# ProPrj_HSLinkTestBoard_2025-10-28.net
KiCad netlist of a schematic drawn in EasyEDA Pro
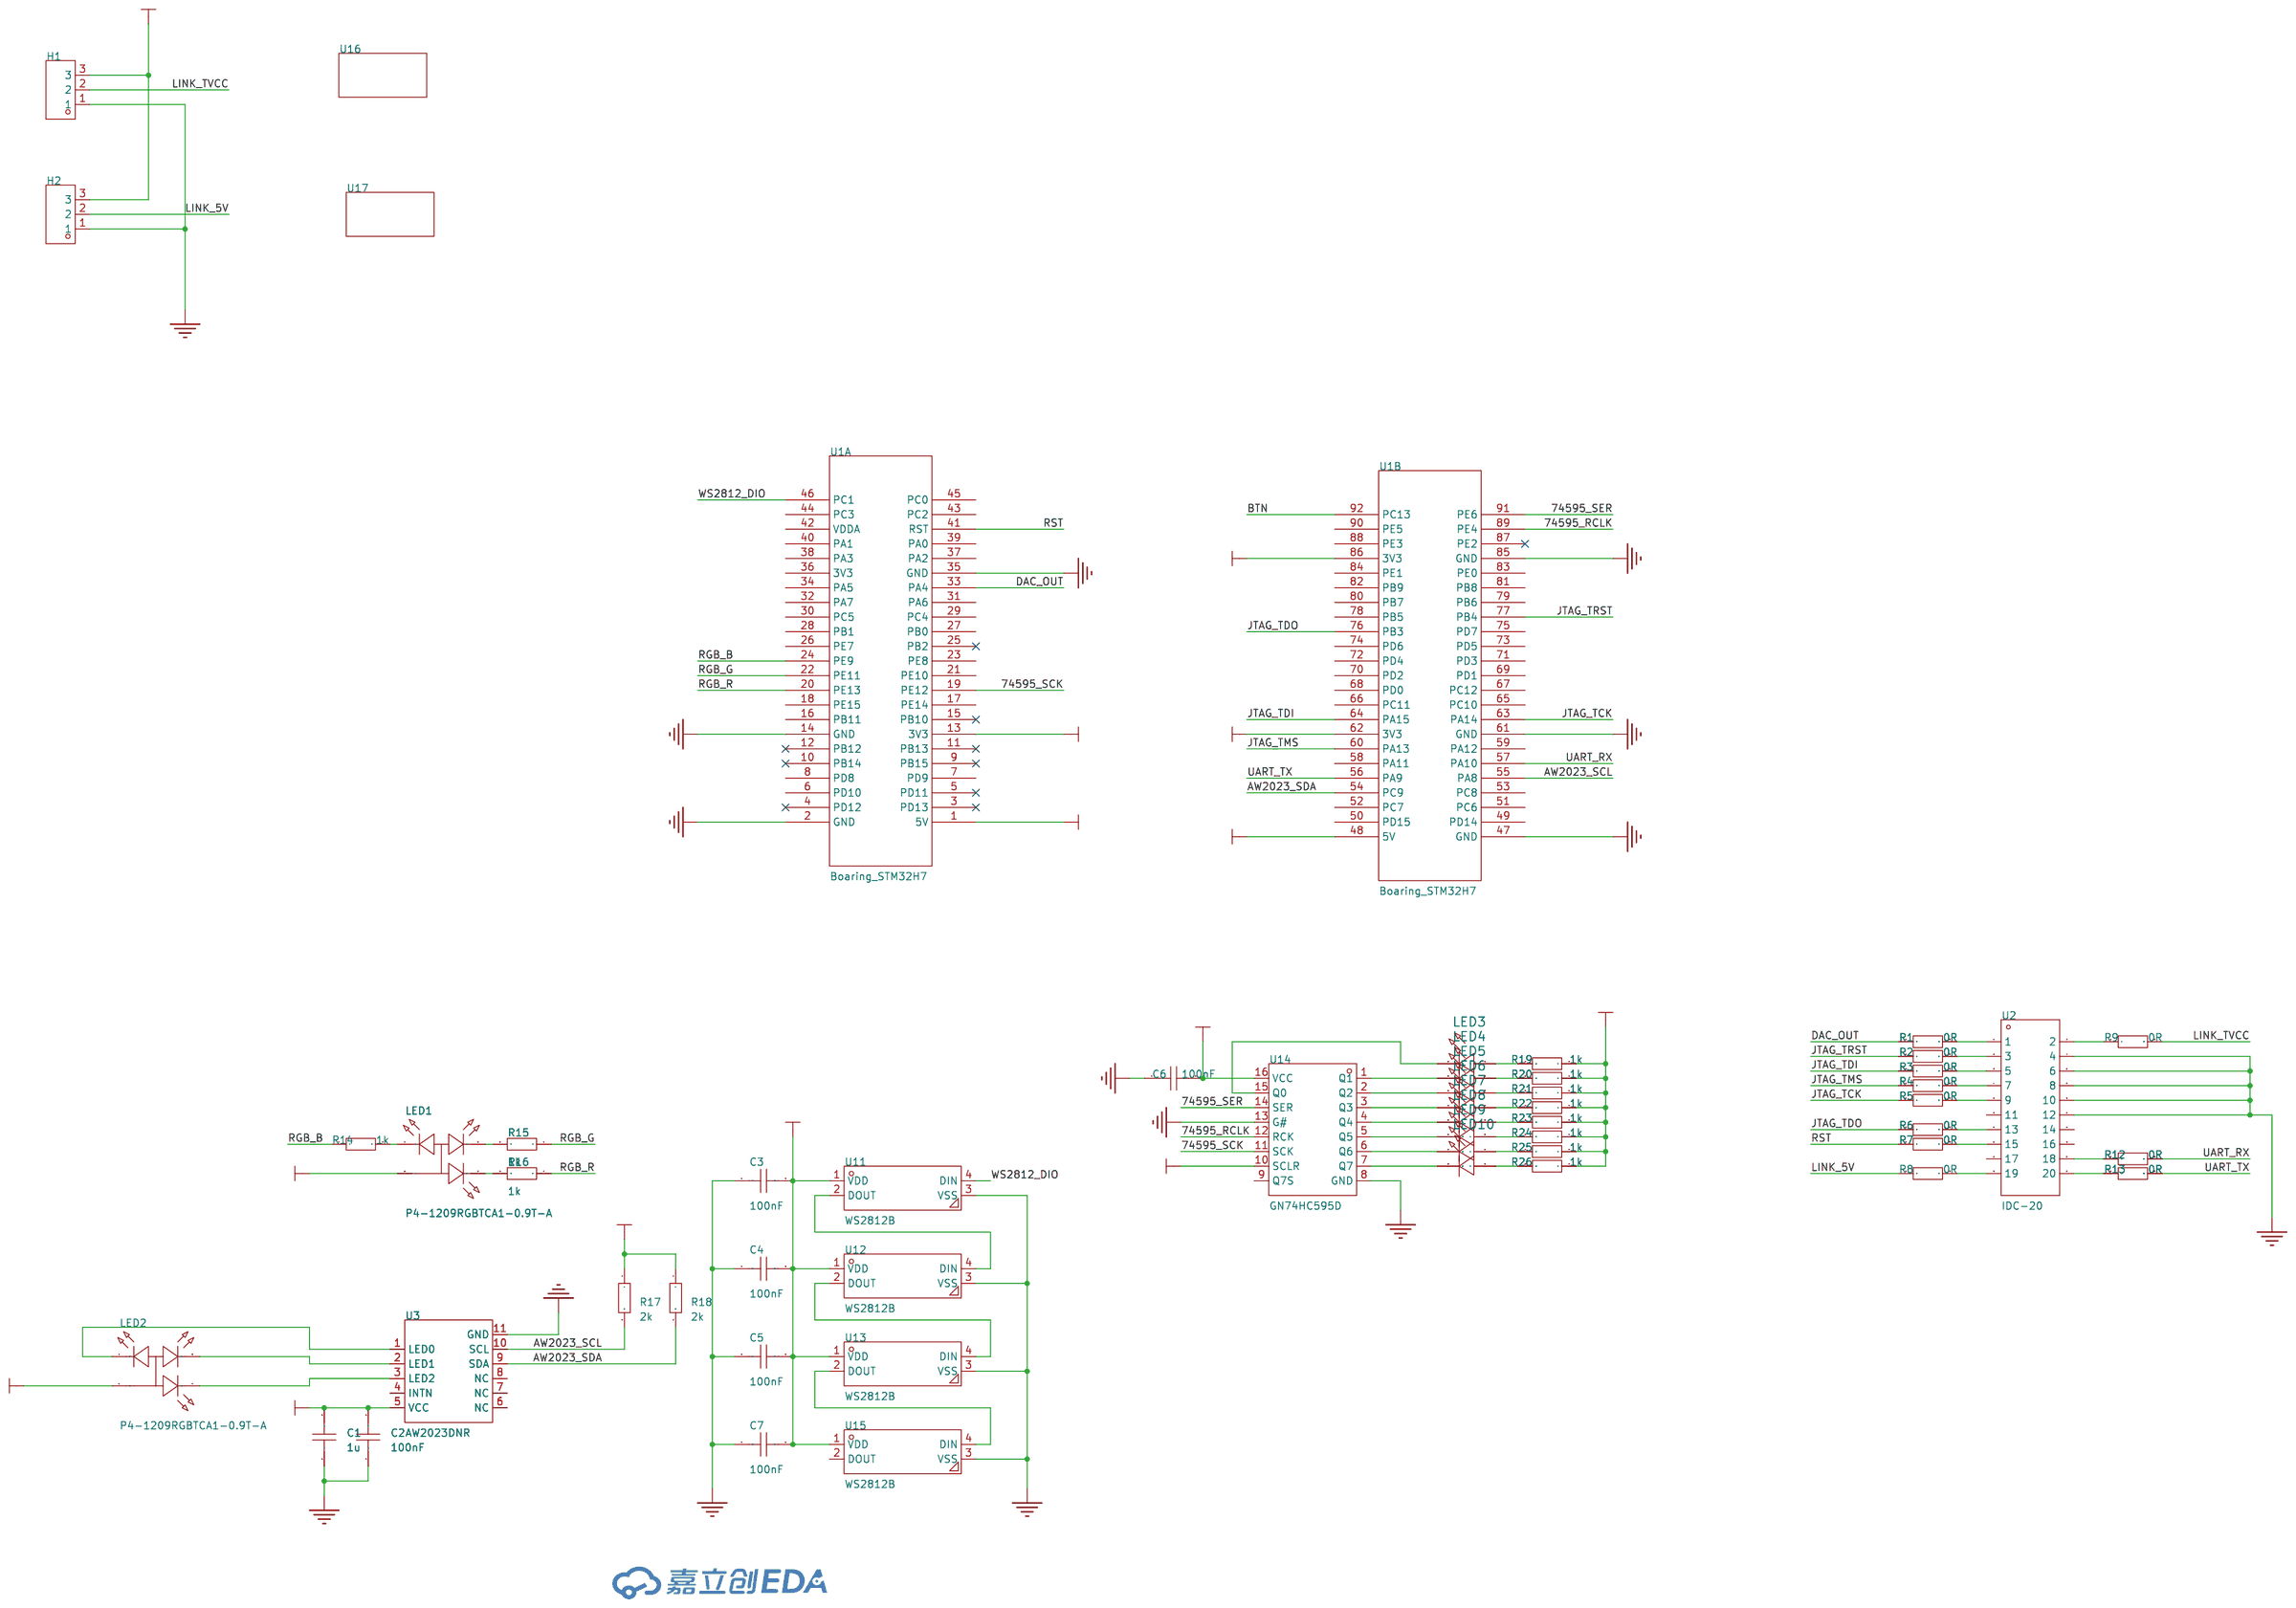
[diagram p0: schematic sheet]

(export (version "E")
  (design (tool "Eeschema 10.0.6"))
  (components
    (comp (ref "C1")
      (value "1u")
      (footprint "easyedapro:C0603")
      (libsource (lib "easyedapro") (part "CapAcitance"))
    )
    (comp (ref "C2")
      (value "100nF")
      (footprint "easyedapro:C0603")
      (libsource (lib "easyedapro") (part "CapAcitance"))
    )
    (comp (ref "C3")
      (value "100nF")
      (footprint "easyedapro:C0603")
      (libsource (lib "easyedapro") (part "CapAcitance"))
    )
    (comp (ref "C4")
      (value "100nF")
      (footprint "easyedapro:C0603")
      (libsource (lib "easyedapro") (part "CapAcitance"))
    )
    (comp (ref "C5")
      (value "100nF")
      (footprint "easyedapro:C0603")
      (libsource (lib "easyedapro") (part "CapAcitance"))
    )
    (comp (ref "C6")
      (value "100nF")
      (footprint "easyedapro:C0603")
      (libsource (lib "easyedapro") (part "CapAcitance"))
    )
    (comp (ref "C7")
      (value "100nF")
      (footprint "easyedapro:C0603")
      (libsource (lib "easyedapro") (part "CapAcitance"))
    )
    (comp (ref "H1")
      (value "~")
      (footprint "easyedapro:HDR-TH_3P-P2.54-V-F")
      (libsource (lib "easyedapro") (part "PM254V-11-03-H85"))
    )
    (comp (ref "H2")
      (value "~")
      (footprint "easyedapro:HDR-TH_3P-P2.54-V-F")
      (libsource (lib "easyedapro") (part "PM254V-11-03-H85"))
    )
    (comp (ref "LED1")
      (value "P4-1209RGBTCA1-0.9T-A")
      (footprint "easyedapro:LED-SMD_4P-L3.2-W2.7-TL-CW")
      (fields (field (name "Manufacturer") "TUOZHAN(拓展光电)"))
      (libsource (lib "easyedapro") (part "P4-1209RGBTCA1-0.9T-A"))
    )
    (comp (ref "LED2")
      (value "P4-1209RGBTCA1-0.9T-A")
      (footprint "easyedapro:LED-SMD_4P-L3.2-W2.7-TL-CW")
      (fields (field (name "Manufacturer") "TUOZHAN(拓展光电)"))
      (libsource (lib "easyedapro") (part "P4-1209RGBTCA1-0.9T-A"))
    )
    (comp (ref "LED3")
      (value "~")
      (footprint "easyedapro:LED_0603")
      (libsource (lib "easyedapro") (part "LED_R"))
    )
    (comp (ref "LED4")
      (value "~")
      (footprint "easyedapro:LED_0603")
      (libsource (lib "easyedapro") (part "LED_R"))
    )
    (comp (ref "LED5")
      (value "~")
      (footprint "easyedapro:LED_0603")
      (libsource (lib "easyedapro") (part "LED_R"))
    )
    (comp (ref "LED6")
      (value "~")
      (footprint "easyedapro:LED_0603")
      (libsource (lib "easyedapro") (part "LED_R"))
    )
    (comp (ref "LED7")
      (value "~")
      (footprint "easyedapro:LED_0603")
      (libsource (lib "easyedapro") (part "LED_R"))
    )
    (comp (ref "LED8")
      (value "~")
      (footprint "easyedapro:LED_0603")
      (libsource (lib "easyedapro") (part "LED_R"))
    )
    (comp (ref "LED9")
      (value "~")
      (footprint "easyedapro:LED_0603")
      (libsource (lib "easyedapro") (part "LED_R"))
    )
    (comp (ref "LED10")
      (value "~")
      (footprint "easyedapro:LED_0603")
      (libsource (lib "easyedapro") (part "LED_R"))
    )
    (comp (ref "R1") (value "0R") (footprint "easyedapro:R0603") (libsource (lib "easyedapro") (part "电阻")))
    (comp (ref "R2") (value "0R") (footprint "easyedapro:R0603") (libsource (lib "easyedapro") (part "电阻")))
    (comp (ref "R3") (value "0R") (footprint "easyedapro:R0603") (libsource (lib "easyedapro") (part "电阻")))
    (comp (ref "R4") (value "0R") (footprint "easyedapro:R0603") (libsource (lib "easyedapro") (part "电阻")))
    (comp (ref "R5") (value "0R") (footprint "easyedapro:R0603") (libsource (lib "easyedapro") (part "电阻")))
    (comp (ref "R6") (value "0R") (footprint "easyedapro:R0603") (libsource (lib "easyedapro") (part "电阻")))
    (comp (ref "R7") (value "0R") (footprint "easyedapro:R0603") (libsource (lib "easyedapro") (part "电阻")))
    (comp (ref "R8") (value "0R") (footprint "easyedapro:R0603") (libsource (lib "easyedapro") (part "电阻")))
    (comp (ref "R9") (value "0R") (footprint "easyedapro:R0603") (libsource (lib "easyedapro") (part "电阻")))
    (comp (ref "R12") (value "0R") (footprint "easyedapro:R0603") (libsource (lib "easyedapro") (part "电阻")))
    (comp (ref "R13") (value "0R") (footprint "easyedapro:R0603") (libsource (lib "easyedapro") (part "电阻")))
    (comp (ref "R14") (value "1k") (footprint "easyedapro:R0603") (libsource (lib "easyedapro") (part "电阻")))
    (comp (ref "R15") (value "1k") (footprint "easyedapro:R0603") (libsource (lib "easyedapro") (part "电阻")))
    (comp (ref "R16") (value "1k") (footprint "easyedapro:R0603") (libsource (lib "easyedapro") (part "电阻")))
    (comp (ref "R17") (value "2k") (footprint "easyedapro:R0603") (libsource (lib "easyedapro") (part "电阻")))
    (comp (ref "R18") (value "2k") (footprint "easyedapro:R0603") (libsource (lib "easyedapro") (part "电阻")))
    (comp (ref "R19") (value "1k") (footprint "easyedapro:R0603") (libsource (lib "easyedapro") (part "电阻")))
    (comp (ref "R20") (value "1k") (footprint "easyedapro:R0603") (libsource (lib "easyedapro") (part "电阻")))
    (comp (ref "R21") (value "1k") (footprint "easyedapro:R0603") (libsource (lib "easyedapro") (part "电阻")))
    (comp (ref "R22") (value "1k") (footprint "easyedapro:R0603") (libsource (lib "easyedapro") (part "电阻")))
    (comp (ref "R23") (value "1k") (footprint "easyedapro:R0603") (libsource (lib "easyedapro") (part "电阻")))
    (comp (ref "R24") (value "1k") (footprint "easyedapro:R0603") (libsource (lib "easyedapro") (part "电阻")))
    (comp (ref "R25") (value "1k") (footprint "easyedapro:R0603") (libsource (lib "easyedapro") (part "电阻")))
    (comp (ref "R26") (value "1k") (footprint "easyedapro:R0603") (libsource (lib "easyedapro") (part "电阻")))
    (comp (ref "U1")
      (value "Boaring_STM32H7")
      (footprint "easyedapro:Boaring_STM32H7")
      (libsource (lib "easyedapro") (part "Boaring_STM32H7"))
    )
    (comp (ref "U2")
      (value "IDC-20")
      (footprint "easyedapro:IDC-TH_20P-P2.54-V-R2-C10-S2.54")
      (libsource (lib "easyedapro") (part "IDC-20"))
    )
    (comp (ref "U3")
      (value "AW2023DNR")
      (footprint "easyedapro:DFN-10_L2.0-W2.0-P0.40-BL-EP")
      (fields (field (name "Manufacturer") "AWINIC(艾为)"))
      (libsource (lib "easyedapro") (part "AW2023DNR"))
    )
    (comp (ref "U11")
      (value "WS2812B")
      (footprint "easyedapro:LED-SMD_4P-L5.0-W5.0-TL")
      (libsource (lib "easyedapro") (part "WS2812B_C9900106807"))
    )
    (comp (ref "U12")
      (value "WS2812B")
      (footprint "easyedapro:LED-SMD_4P-L5.0-W5.0-TL")
      (libsource (lib "easyedapro") (part "WS2812B_C9900106807"))
    )
    (comp (ref "U13")
      (value "WS2812B")
      (footprint "easyedapro:LED-SMD_4P-L5.0-W5.0-TL")
      (libsource (lib "easyedapro") (part "WS2812B_C9900106807"))
    )
    (comp (ref "U14")
      (value "GN74HC595D")
      (footprint "easyedapro:SOP-16_L9.9-W3.9-P1.27-LS6.0-BL")
      (description "低噪声、低功耗、高速的COMS移位寄存器，能够驱动15个LS-TTL的负载。8位串行输入，并行输出的移位寄存器及带有三态输出控制的8位D行储存器。")
      (fields (field (name "Manufacturer") "GN(旌芯半导体)"))
      (libsource (lib "easyedapro") (part "GN74HC595D"))
    )
    (comp (ref "U15")
      (value "WS2812B")
      (footprint "easyedapro:LED-SMD_4P-L5.0-W5.0-TL")
      (libsource (lib "easyedapro") (part "WS2812B_C9900106807"))
    )
    (comp (ref "U16")
      (value "~")
      (footprint "easyedapro:0.36寸裸表")
      (libsource (lib "easyedapro") (part "0.36裸表"))
    )
    (comp (ref "U17")
      (value "~")
      (footprint "easyedapro:0.36寸裸表")
      (libsource (lib "easyedapro") (part "0.36裸表"))
    )
  )
  (nets
    (net (code "1") (name "/74595_RCLK") (class "Default")
      (node (ref "U1") (pin "89") (pinfunction "PE4_89") (pintype "unspecified"))
      (node (ref "U14") (pin "12") (pinfunction "RCK_12") (pintype "unspecified"))
    )
    (net (code "2") (name "/74595_SCK") (class "Default")
      (node (ref "U1") (pin "19") (pinfunction "PE12_19") (pintype "unspecified"))
      (node (ref "U14") (pin "11") (pinfunction "SCK_11") (pintype "unspecified"))
    )
    (net (code "3") (name "/74595_SER") (class "Default")
      (node (ref "U1") (pin "91") (pinfunction "PE6_91") (pintype "unspecified"))
      (node (ref "U14") (pin "14") (pinfunction "SER_14") (pintype "unspecified"))
    )
    (net (code "4") (name "/AW2023_SCL") (class "Default")
      (node (ref "R17") (pin "2") (pinfunction "2_2") (pintype "input"))
      (node (ref "U1") (pin "55") (pinfunction "PA8_55") (pintype "unspecified"))
      (node (ref "U3") (pin "10") (pinfunction "SCL_10") (pintype "unspecified"))
    )
    (net (code "5") (name "/AW2023_SDA") (class "Default")
      (node (ref "R18") (pin "2") (pinfunction "2_2") (pintype "input"))
      (node (ref "U1") (pin "54") (pinfunction "PC9_54") (pintype "unspecified"))
      (node (ref "U3") (pin "9") (pinfunction "SDA_9") (pintype "unspecified"))
    )
    (net (code "6") (name "/BTN") (class "Default")
      (node (ref "U1") (pin "92") (pinfunction "PC13_92") (pintype "unspecified"))
    )
    (net (code "7") (name "/DAC_OUT") (class "Default")
      (node (ref "R1") (pin "1") (pinfunction "1_1") (pintype "input"))
      (node (ref "U1") (pin "33") (pinfunction "PA4_33") (pintype "unspecified"))
    )
    (net (code "8") (name "/JTAG_TCK") (class "Default")
      (node (ref "R5") (pin "1") (pinfunction "1_1") (pintype "input"))
      (node (ref "U1") (pin "63") (pinfunction "PA14_63") (pintype "unspecified"))
    )
    (net (code "9") (name "/JTAG_TDI") (class "Default")
      (node (ref "R3") (pin "1") (pinfunction "1_1") (pintype "input"))
      (node (ref "U1") (pin "64") (pinfunction "PA15_64") (pintype "unspecified"))
    )
    (net (code "10") (name "/JTAG_TDO") (class "Default")
      (node (ref "R6") (pin "1") (pinfunction "1_1") (pintype "input"))
      (node (ref "U1") (pin "76") (pinfunction "PB3_76") (pintype "unspecified"))
    )
    (net (code "11") (name "/JTAG_TMS") (class "Default")
      (node (ref "R4") (pin "1") (pinfunction "1_1") (pintype "input"))
      (node (ref "U1") (pin "60") (pinfunction "PA13_60") (pintype "unspecified"))
    )
    (net (code "12") (name "/JTAG_TRST") (class "Default")
      (node (ref "R2") (pin "1") (pinfunction "1_1") (pintype "input"))
      (node (ref "U1") (pin "77") (pinfunction "PB4_77") (pintype "unspecified"))
    )
    (net (code "13") (name "/LINK_5V") (class "Default")
      (node (ref "H2") (pin "2") (pinfunction "2_2") (pintype "unspecified"))
      (node (ref "R8") (pin "1") (pinfunction "1_1") (pintype "input"))
    )
    (net (code "14") (name "/LINK_TVCC") (class "Default")
      (node (ref "H1") (pin "2") (pinfunction "2_2") (pintype "unspecified"))
      (node (ref "R9") (pin "2") (pinfunction "2_2") (pintype "input"))
    )
    (net (code "15") (name "/RGB_B") (class "Default")
      (node (ref "R14") (pin "1") (pinfunction "1_1") (pintype "input"))
      (node (ref "U1") (pin "24") (pinfunction "PE9_24") (pintype "unspecified"))
    )
    (net (code "16") (name "/RGB_G") (class "Default")
      (node (ref "R15") (pin "1") (pinfunction "1_1") (pintype "input"))
      (node (ref "U1") (pin "22") (pinfunction "PE11_22") (pintype "unspecified"))
    )
    (net (code "17") (name "/RGB_R") (class "Default")
      (node (ref "R16") (pin "1") (pinfunction "1_1") (pintype "input"))
      (node (ref "U1") (pin "20") (pinfunction "PE13_20") (pintype "unspecified"))
    )
    (net (code "18") (name "/RST") (class "Default")
      (node (ref "R7") (pin "1") (pinfunction "1_1") (pintype "input"))
      (node (ref "U1") (pin "41") (pinfunction "RST_41") (pintype "unspecified"))
    )
    (net (code "19") (name "/UART_RX") (class "Default")
      (node (ref "R12") (pin "2") (pinfunction "2_2") (pintype "input"))
      (node (ref "U1") (pin "57") (pinfunction "PA10_57") (pintype "unspecified"))
    )
    (net (code "20") (name "/UART_TX") (class "Default")
      (node (ref "R13") (pin "2") (pinfunction "2_2") (pintype "input"))
      (node (ref "U1") (pin "56") (pinfunction "PA9_56") (pintype "unspecified"))
    )
    (net (code "21") (name "/WS2812_DIO") (class "Default")
      (node (ref "U1") (pin "46") (pinfunction "PC1_46") (pintype "unspecified"))
      (node (ref "U11") (pin "4") (pinfunction "DIN_4") (pintype "unspecified"))
    )
    (net (code "22") (name "3.3V") (class "Default")
      (node (ref "C1") (pin "2") (pinfunction "2_2") (pintype "input"))
      (node (ref "C2") (pin "2") (pinfunction "2_2") (pintype "input"))
      (node (ref "C6") (pin "2") (pinfunction "2_2") (pintype "input"))
      (node (ref "LED1") (pin "3") (pinfunction "A_3") (pintype "unspecified"))
      (node (ref "LED2") (pin "3") (pinfunction "A_3") (pintype "unspecified"))
      (node (ref "R17") (pin "1") (pinfunction "1_1") (pintype "input"))
      (node (ref "R18") (pin "1") (pinfunction "1_1") (pintype "input"))
      (node (ref "R19") (pin "1") (pinfunction "1_1") (pintype "input"))
      (node (ref "R20") (pin "1") (pinfunction "1_1") (pintype "input"))
      (node (ref "R21") (pin "1") (pinfunction "1_1") (pintype "input"))
      (node (ref "R22") (pin "1") (pinfunction "1_1") (pintype "input"))
      (node (ref "R23") (pin "1") (pinfunction "1_1") (pintype "input"))
      (node (ref "R24") (pin "1") (pinfunction "1_1") (pintype "input"))
      (node (ref "R25") (pin "1") (pinfunction "1_1") (pintype "input"))
      (node (ref "R26") (pin "1") (pinfunction "1_1") (pintype "input"))
      (node (ref "U1") (pin "13") (pinfunction "3V3_13") (pintype "unspecified"))
      (node (ref "U1") (pin "62") (pinfunction "3V3_62") (pintype "unspecified"))
      (node (ref "U1") (pin "86") (pinfunction "3V3_86") (pintype "unspecified"))
      (node (ref "U14") (pin "10") (pinfunction "SCLR_10") (pintype "unspecified"))
      (node (ref "U14") (pin "16") (pinfunction "VCC_16") (pintype "unspecified"))
      (node (ref "U3") (pin "5") (pinfunction "VCC_5") (pintype "unspecified"))
    )
    (net (code "23") (name "5V") (class "Default")
      (node (ref "C3") (pin "2") (pinfunction "2_2") (pintype "input"))
      (node (ref "C4") (pin "2") (pinfunction "2_2") (pintype "input"))
      (node (ref "C5") (pin "2") (pinfunction "2_2") (pintype "input"))
      (node (ref "C7") (pin "2") (pinfunction "2_2") (pintype "input"))
      (node (ref "H1") (pin "3") (pinfunction "3_3") (pintype "unspecified"))
      (node (ref "H2") (pin "3") (pinfunction "3_3") (pintype "unspecified"))
      (node (ref "U1") (pin "1") (pinfunction "5V_1") (pintype "unspecified"))
      (node (ref "U1") (pin "48") (pinfunction "5V_48") (pintype "unspecified"))
      (node (ref "U11") (pin "1") (pinfunction "VDD_1") (pintype "unspecified"))
      (node (ref "U12") (pin "1") (pinfunction "VDD_1") (pintype "unspecified"))
      (node (ref "U13") (pin "1") (pinfunction "VDD_1") (pintype "unspecified"))
      (node (ref "U15") (pin "1") (pinfunction "VDD_1") (pintype "unspecified"))
    )
    (net (code "24") (name "GND") (class "Default")
      (node (ref "C1") (pin "1") (pinfunction "1_1") (pintype "input"))
      (node (ref "C2") (pin "1") (pinfunction "1_1") (pintype "input"))
      (node (ref "C3") (pin "1") (pinfunction "1_1") (pintype "input"))
      (node (ref "C4") (pin "1") (pinfunction "1_1") (pintype "input"))
      (node (ref "C5") (pin "1") (pinfunction "1_1") (pintype "input"))
      (node (ref "C6") (pin "1") (pinfunction "1_1") (pintype "input"))
      (node (ref "C7") (pin "1") (pinfunction "1_1") (pintype "input"))
      (node (ref "H1") (pin "1") (pinfunction "1_1") (pintype "unspecified"))
      (node (ref "H2") (pin "1") (pinfunction "1_1") (pintype "unspecified"))
      (node (ref "U1") (pin "14") (pinfunction "GND_14") (pintype "unspecified"))
      (node (ref "U1") (pin "2") (pinfunction "GND_2") (pintype "unspecified"))
      (node (ref "U1") (pin "35") (pinfunction "GND_35") (pintype "unspecified"))
      (node (ref "U1") (pin "47") (pinfunction "GND_47") (pintype "unspecified"))
      (node (ref "U1") (pin "61") (pinfunction "GND_61") (pintype "unspecified"))
      (node (ref "U1") (pin "85") (pinfunction "GND_85") (pintype "unspecified"))
      (node (ref "U11") (pin "3") (pinfunction "VSS_3") (pintype "unspecified"))
      (node (ref "U12") (pin "3") (pinfunction "VSS_3") (pintype "unspecified"))
      (node (ref "U13") (pin "3") (pinfunction "VSS_3") (pintype "unspecified"))
      (node (ref "U14") (pin "13") (pinfunction "G#_13") (pintype "unspecified"))
      (node (ref "U14") (pin "8") (pinfunction "GND_8") (pintype "unspecified"))
      (node (ref "U15") (pin "3") (pinfunction "VSS_3") (pintype "unspecified"))
      (node (ref "U2") (pin "10") (pinfunction "10_10") (pintype "unspecified"))
      (node (ref "U2") (pin "12") (pinfunction "12_12") (pintype "unspecified"))
      (node (ref "U2") (pin "4") (pinfunction "4_4") (pintype "unspecified"))
      (node (ref "U2") (pin "6") (pinfunction "6_6") (pintype "unspecified"))
      (node (ref "U2") (pin "8") (pinfunction "8_8") (pintype "unspecified"))
      (node (ref "U3") (pin "11") (pinfunction "GND_11") (pintype "unspecified"))
    )
    (net (code "25") (name "Net-(LED1-K-Pad1)") (class "Default")
      (node (ref "LED1") (pin "1") (pinfunction "K_1") (pintype "unspecified"))
      (node (ref "R14") (pin "2") (pinfunction "2_2") (pintype "input"))
    )
    (net (code "26") (name "Net-(LED1-K-Pad2)") (class "Default")
      (node (ref "LED1") (pin "2") (pinfunction "K_2") (pintype "unspecified"))
      (node (ref "R15") (pin "2") (pinfunction "2_2") (pintype "input"))
    )
    (net (code "27") (name "Net-(LED1-K-Pad4)") (class "Default")
      (node (ref "LED1") (pin "4") (pinfunction "K_4") (pintype "unspecified"))
      (node (ref "R16") (pin "2") (pinfunction "2_2") (pintype "input"))
    )
    (net (code "28") (name "Net-(LED3-A)") (class "Default")
      (node (ref "LED3") (pin "2") (pinfunction "A_2") (pintype "input"))
      (node (ref "R19") (pin "2") (pinfunction "2_2") (pintype "input"))
    )
    (net (code "29") (name "Net-(LED3-C)") (class "Default")
      (node (ref "LED3") (pin "1") (pinfunction "C_1") (pintype "input"))
      (node (ref "U14") (pin "15") (pinfunction "Q0_15") (pintype "unspecified"))
    )
    (net (code "30") (name "Net-(LED4-A)") (class "Default")
      (node (ref "LED4") (pin "2") (pinfunction "A_2") (pintype "input"))
      (node (ref "R20") (pin "2") (pinfunction "2_2") (pintype "input"))
    )
    (net (code "31") (name "Net-(LED4-C)") (class "Default")
      (node (ref "LED4") (pin "1") (pinfunction "C_1") (pintype "input"))
      (node (ref "U14") (pin "1") (pinfunction "Q1_1") (pintype "unspecified"))
    )
    (net (code "32") (name "Net-(LED5-A)") (class "Default")
      (node (ref "LED5") (pin "2") (pinfunction "A_2") (pintype "input"))
      (node (ref "R21") (pin "2") (pinfunction "2_2") (pintype "input"))
    )
    (net (code "33") (name "Net-(LED5-C)") (class "Default")
      (node (ref "LED5") (pin "1") (pinfunction "C_1") (pintype "input"))
      (node (ref "U14") (pin "2") (pinfunction "Q2_2") (pintype "unspecified"))
    )
    (net (code "34") (name "Net-(LED6-A)") (class "Default")
      (node (ref "LED6") (pin "2") (pinfunction "A_2") (pintype "input"))
      (node (ref "R22") (pin "2") (pinfunction "2_2") (pintype "input"))
    )
    (net (code "35") (name "Net-(LED6-C)") (class "Default")
      (node (ref "LED6") (pin "1") (pinfunction "C_1") (pintype "input"))
      (node (ref "U14") (pin "3") (pinfunction "Q3_3") (pintype "unspecified"))
    )
    (net (code "36") (name "Net-(LED7-A)") (class "Default")
      (node (ref "LED7") (pin "2") (pinfunction "A_2") (pintype "input"))
      (node (ref "R23") (pin "2") (pinfunction "2_2") (pintype "input"))
    )
    (net (code "37") (name "Net-(LED7-C)") (class "Default")
      (node (ref "LED7") (pin "1") (pinfunction "C_1") (pintype "input"))
      (node (ref "U14") (pin "4") (pinfunction "Q4_4") (pintype "unspecified"))
    )
    (net (code "38") (name "Net-(LED8-A)") (class "Default")
      (node (ref "LED8") (pin "2") (pinfunction "A_2") (pintype "input"))
      (node (ref "R24") (pin "2") (pinfunction "2_2") (pintype "input"))
    )
    (net (code "39") (name "Net-(LED8-C)") (class "Default")
      (node (ref "LED8") (pin "1") (pinfunction "C_1") (pintype "input"))
      (node (ref "U14") (pin "5") (pinfunction "Q5_5") (pintype "unspecified"))
    )
    (net (code "40") (name "Net-(LED9-A)") (class "Default")
      (node (ref "LED9") (pin "2") (pinfunction "A_2") (pintype "input"))
      (node (ref "R25") (pin "2") (pinfunction "2_2") (pintype "input"))
    )
    (net (code "41") (name "Net-(LED9-C)") (class "Default")
      (node (ref "LED9") (pin "1") (pinfunction "C_1") (pintype "input"))
      (node (ref "U14") (pin "6") (pinfunction "Q6_6") (pintype "unspecified"))
    )
    (net (code "42") (name "Net-(LED10-A)") (class "Default")
      (node (ref "LED10") (pin "2") (pinfunction "A_2") (pintype "input"))
      (node (ref "R26") (pin "2") (pinfunction "2_2") (pintype "input"))
    )
    (net (code "43") (name "Net-(LED10-C)") (class "Default")
      (node (ref "LED10") (pin "1") (pinfunction "C_1") (pintype "input"))
      (node (ref "U14") (pin "7") (pinfunction "Q7_7") (pintype "unspecified"))
    )
    (net (code "44") (name "Net-(R1-Pad2)") (class "Default")
      (node (ref "R1") (pin "2") (pinfunction "2_2") (pintype "input"))
      (node (ref "U2") (pin "1") (pinfunction "1_1") (pintype "unspecified"))
    )
    (net (code "45") (name "Net-(R2-Pad2)") (class "Default")
      (node (ref "R2") (pin "2") (pinfunction "2_2") (pintype "input"))
      (node (ref "U2") (pin "3") (pinfunction "3_3") (pintype "unspecified"))
    )
    (net (code "46") (name "Net-(R3-Pad2)") (class "Default")
      (node (ref "R3") (pin "2") (pinfunction "2_2") (pintype "input"))
      (node (ref "U2") (pin "5") (pinfunction "5_5") (pintype "unspecified"))
    )
    (net (code "47") (name "Net-(R4-Pad2)") (class "Default")
      (node (ref "R4") (pin "2") (pinfunction "2_2") (pintype "input"))
      (node (ref "U2") (pin "7") (pinfunction "7_7") (pintype "unspecified"))
    )
    (net (code "48") (name "Net-(R5-Pad2)") (class "Default")
      (node (ref "R5") (pin "2") (pinfunction "2_2") (pintype "input"))
      (node (ref "U2") (pin "9") (pinfunction "9_9") (pintype "unspecified"))
    )
    (net (code "49") (name "Net-(R6-Pad2)") (class "Default")
      (node (ref "R6") (pin "2") (pinfunction "2_2") (pintype "input"))
      (node (ref "U2") (pin "13") (pinfunction "13_13") (pintype "unspecified"))
    )
    (net (code "50") (name "Net-(R7-Pad2)") (class "Default")
      (node (ref "R7") (pin "2") (pinfunction "2_2") (pintype "input"))
      (node (ref "U2") (pin "15") (pinfunction "15_15") (pintype "unspecified"))
    )
    (net (code "51") (name "Net-(R8-Pad2)") (class "Default")
      (node (ref "R8") (pin "2") (pinfunction "2_2") (pintype "input"))
      (node (ref "U2") (pin "19") (pinfunction "19_19") (pintype "unspecified"))
    )
    (net (code "52") (name "Net-(R9-Pad1)") (class "Default")
      (node (ref "R9") (pin "1") (pinfunction "1_1") (pintype "input"))
      (node (ref "U2") (pin "2") (pinfunction "2_2") (pintype "unspecified"))
    )
    (net (code "53") (name "Net-(R12-Pad1)") (class "Default")
      (node (ref "R12") (pin "1") (pinfunction "1_1") (pintype "input"))
      (node (ref "U2") (pin "18") (pinfunction "18_18") (pintype "unspecified"))
    )
    (net (code "54") (name "Net-(R13-Pad1)") (class "Default")
      (node (ref "R13") (pin "1") (pinfunction "1_1") (pintype "input"))
      (node (ref "U2") (pin "20") (pinfunction "20_20") (pintype "unspecified"))
    )
    (net (code "55") (name "Net-(U3-LED0)") (class "Default")
      (node (ref "LED2") (pin "1") (pinfunction "K_1") (pintype "unspecified"))
      (node (ref "U3") (pin "1") (pinfunction "LED0_1") (pintype "unspecified"))
    )
    (net (code "56") (name "Net-(U3-LED1)") (class "Default")
      (node (ref "LED2") (pin "2") (pinfunction "K_2") (pintype "unspecified"))
      (node (ref "U3") (pin "2") (pinfunction "LED1_2") (pintype "unspecified"))
    )
    (net (code "57") (name "Net-(U3-LED2)") (class "Default")
      (node (ref "LED2") (pin "4") (pinfunction "K_4") (pintype "unspecified"))
      (node (ref "U3") (pin "3") (pinfunction "LED2_3") (pintype "unspecified"))
    )
    (net (code "58") (name "Net-(U11-DOUT)") (class "Default")
      (node (ref "U11") (pin "2") (pinfunction "DOUT_2") (pintype "unspecified"))
      (node (ref "U12") (pin "4") (pinfunction "DIN_4") (pintype "unspecified"))
    )
    (net (code "59") (name "Net-(U12-DOUT)") (class "Default")
      (node (ref "U12") (pin "2") (pinfunction "DOUT_2") (pintype "unspecified"))
      (node (ref "U13") (pin "4") (pinfunction "DIN_4") (pintype "unspecified"))
    )
    (net (code "60") (name "Net-(U13-DOUT)") (class "Default")
      (node (ref "U13") (pin "2") (pinfunction "DOUT_2") (pintype "unspecified"))
      (node (ref "U15") (pin "4") (pinfunction "DIN_4") (pintype "unspecified"))
    )
    (net (code "61") (name "unconnected-(U1A-3V3-Pad36)") (class "Default")
      (node (ref "U1") (pin "36") (pinfunction "3V3_36") (pintype "unspecified"))
    )
    (net (code "62") (name "unconnected-(U1A-PA0-Pad39)") (class "Default")
      (node (ref "U1") (pin "39") (pinfunction "PA0_39") (pintype "unspecified"))
    )
    (net (code "63") (name "unconnected-(U1A-PA1-Pad40)") (class "Default")
      (node (ref "U1") (pin "40") (pinfunction "PA1_40") (pintype "unspecified"))
    )
    (net (code "64") (name "unconnected-(U1A-PA2-Pad37)") (class "Default")
      (node (ref "U1") (pin "37") (pinfunction "PA2_37") (pintype "unspecified"))
    )
    (net (code "65") (name "unconnected-(U1A-PA3-Pad38)") (class "Default")
      (node (ref "U1") (pin "38") (pinfunction "PA3_38") (pintype "unspecified"))
    )
    (net (code "66") (name "unconnected-(U1A-PA5-Pad34)") (class "Default")
      (node (ref "U1") (pin "34") (pinfunction "PA5_34") (pintype "unspecified"))
    )
    (net (code "67") (name "unconnected-(U1A-PA6-Pad31)") (class "Default")
      (node (ref "U1") (pin "31") (pinfunction "PA6_31") (pintype "unspecified"))
    )
    (net (code "68") (name "unconnected-(U1A-PA7-Pad32)") (class "Default")
      (node (ref "U1") (pin "32") (pinfunction "PA7_32") (pintype "unspecified"))
    )
    (net (code "69") (name "unconnected-(U1A-PB0-Pad27)") (class "Default")
      (node (ref "U1") (pin "27") (pinfunction "PB0_27") (pintype "unspecified"))
    )
    (net (code "70") (name "unconnected-(U1A-PB1-Pad28)") (class "Default")
      (node (ref "U1") (pin "28") (pinfunction "PB1_28") (pintype "unspecified"))
    )
    (net (code "71") (name "unconnected-(U1A-PB2-Pad25)") (class "Default")
      (node (ref "U1") (pin "25") (pinfunction "PB2_25") (pintype "unspecified+no_connect"))
    )
    (net (code "72") (name "unconnected-(U1A-PB10-Pad15)") (class "Default")
      (node (ref "U1") (pin "15") (pinfunction "PB10_15") (pintype "unspecified+no_connect"))
    )
    (net (code "73") (name "unconnected-(U1A-PB11-Pad16)") (class "Default")
      (node (ref "U1") (pin "16") (pinfunction "PB11_16") (pintype "unspecified"))
    )
    (net (code "74") (name "unconnected-(U1A-PB12-Pad12)") (class "Default")
      (node (ref "U1") (pin "12") (pinfunction "PB12_12") (pintype "unspecified+no_connect"))
    )
    (net (code "75") (name "unconnected-(U1A-PB13-Pad11)") (class "Default")
      (node (ref "U1") (pin "11") (pinfunction "PB13_11") (pintype "unspecified+no_connect"))
    )
    (net (code "76") (name "unconnected-(U1A-PB14-Pad10)") (class "Default")
      (node (ref "U1") (pin "10") (pinfunction "PB14_10") (pintype "unspecified+no_connect"))
    )
    (net (code "77") (name "unconnected-(U1A-PB15-Pad9)") (class "Default")
      (node (ref "U1") (pin "9") (pinfunction "PB15_9") (pintype "unspecified+no_connect"))
    )
    (net (code "78") (name "unconnected-(U1A-PC0-Pad45)") (class "Default")
      (node (ref "U1") (pin "45") (pinfunction "PC0_45") (pintype "unspecified"))
    )
    (net (code "79") (name "unconnected-(U1A-PC2-Pad43)") (class "Default")
      (node (ref "U1") (pin "43") (pinfunction "PC2_43") (pintype "unspecified"))
    )
    (net (code "80") (name "unconnected-(U1A-PC3-Pad44)") (class "Default")
      (node (ref "U1") (pin "44") (pinfunction "PC3_44") (pintype "unspecified"))
    )
    (net (code "81") (name "unconnected-(U1A-PC4-Pad29)") (class "Default")
      (node (ref "U1") (pin "29") (pinfunction "PC4_29") (pintype "unspecified"))
    )
    (net (code "82") (name "unconnected-(U1A-PC5-Pad30)") (class "Default")
      (node (ref "U1") (pin "30") (pinfunction "PC5_30") (pintype "unspecified"))
    )
    (net (code "83") (name "unconnected-(U1A-PD8-Pad8)") (class "Default")
      (node (ref "U1") (pin "8") (pinfunction "PD8_8") (pintype "unspecified"))
    )
    (net (code "84") (name "unconnected-(U1A-PD9-Pad7)") (class "Default")
      (node (ref "U1") (pin "7") (pinfunction "PD9_7") (pintype "unspecified"))
    )
    (net (code "85") (name "unconnected-(U1A-PD10-Pad6)") (class "Default")
      (node (ref "U1") (pin "6") (pinfunction "PD10_6") (pintype "unspecified"))
    )
    (net (code "86") (name "unconnected-(U1A-PD11-Pad5)") (class "Default")
      (node (ref "U1") (pin "5") (pinfunction "PD11_5") (pintype "unspecified+no_connect"))
    )
    (net (code "87") (name "unconnected-(U1A-PD12-Pad4)") (class "Default")
      (node (ref "U1") (pin "4") (pinfunction "PD12_4") (pintype "unspecified+no_connect"))
    )
    (net (code "88") (name "unconnected-(U1A-PD13-Pad3)") (class "Default")
      (node (ref "U1") (pin "3") (pinfunction "PD13_3") (pintype "unspecified+no_connect"))
    )
    (net (code "89") (name "unconnected-(U1A-PE7-Pad26)") (class "Default")
      (node (ref "U1") (pin "26") (pinfunction "PE7_26") (pintype "unspecified"))
    )
    (net (code "90") (name "unconnected-(U1A-PE8-Pad23)") (class "Default")
      (node (ref "U1") (pin "23") (pinfunction "PE8_23") (pintype "unspecified"))
    )
    (net (code "91") (name "unconnected-(U1A-PE10-Pad21)") (class "Default")
      (node (ref "U1") (pin "21") (pinfunction "PE10_21") (pintype "unspecified"))
    )
    (net (code "92") (name "unconnected-(U1A-PE14-Pad17)") (class "Default")
      (node (ref "U1") (pin "17") (pinfunction "PE14_17") (pintype "unspecified"))
    )
    (net (code "93") (name "unconnected-(U1A-PE15-Pad18)") (class "Default")
      (node (ref "U1") (pin "18") (pinfunction "PE15_18") (pintype "unspecified"))
    )
    (net (code "94") (name "unconnected-(U1A-VDDA-Pad42)") (class "Default")
      (node (ref "U1") (pin "42") (pinfunction "VDDA_42") (pintype "unspecified"))
    )
    (net (code "95") (name "unconnected-(U1B-PA11-Pad58)") (class "Default")
      (node (ref "U1") (pin "58") (pinfunction "PA11_58") (pintype "unspecified"))
    )
    (net (code "96") (name "unconnected-(U1B-PA12-Pad59)") (class "Default")
      (node (ref "U1") (pin "59") (pinfunction "PA12_59") (pintype "unspecified"))
    )
    (net (code "97") (name "unconnected-(U1B-PB5-Pad78)") (class "Default")
      (node (ref "U1") (pin "78") (pinfunction "PB5_78") (pintype "unspecified"))
    )
    (net (code "98") (name "unconnected-(U1B-PB6-Pad79)") (class "Default")
      (node (ref "U1") (pin "79") (pinfunction "PB6_79") (pintype "unspecified"))
    )
    (net (code "99") (name "unconnected-(U1B-PB7-Pad80)") (class "Default")
      (node (ref "U1") (pin "80") (pinfunction "PB7_80") (pintype "unspecified"))
    )
    (net (code "100") (name "unconnected-(U1B-PB8-Pad81)") (class "Default")
      (node (ref "U1") (pin "81") (pinfunction "PB8_81") (pintype "unspecified"))
    )
    (net (code "101") (name "unconnected-(U1B-PB9-Pad82)") (class "Default")
      (node (ref "U1") (pin "82") (pinfunction "PB9_82") (pintype "unspecified"))
    )
    (net (code "102") (name "unconnected-(U1B-PC6-Pad51)") (class "Default")
      (node (ref "U1") (pin "51") (pinfunction "PC6_51") (pintype "unspecified"))
    )
    (net (code "103") (name "unconnected-(U1B-PC7-Pad52)") (class "Default")
      (node (ref "U1") (pin "52") (pinfunction "PC7_52") (pintype "unspecified"))
    )
    (net (code "104") (name "unconnected-(U1B-PC8-Pad53)") (class "Default")
      (node (ref "U1") (pin "53") (pinfunction "PC8_53") (pintype "unspecified"))
    )
    (net (code "105") (name "unconnected-(U1B-PC10-Pad65)") (class "Default")
      (node (ref "U1") (pin "65") (pinfunction "PC10_65") (pintype "unspecified"))
    )
    (net (code "106") (name "unconnected-(U1B-PC11-Pad66)") (class "Default")
      (node (ref "U1") (pin "66") (pinfunction "PC11_66") (pintype "unspecified"))
    )
    (net (code "107") (name "unconnected-(U1B-PC12-Pad67)") (class "Default")
      (node (ref "U1") (pin "67") (pinfunction "PC12_67") (pintype "unspecified"))
    )
    (net (code "108") (name "unconnected-(U1B-PD0-Pad68)") (class "Default")
      (node (ref "U1") (pin "68") (pinfunction "PD0_68") (pintype "unspecified"))
    )
    (net (code "109") (name "unconnected-(U1B-PD1-Pad69)") (class "Default")
      (node (ref "U1") (pin "69") (pinfunction "PD1_69") (pintype "unspecified"))
    )
    (net (code "110") (name "unconnected-(U1B-PD2-Pad70)") (class "Default")
      (node (ref "U1") (pin "70") (pinfunction "PD2_70") (pintype "unspecified"))
    )
    (net (code "111") (name "unconnected-(U1B-PD3-Pad71)") (class "Default")
      (node (ref "U1") (pin "71") (pinfunction "PD3_71") (pintype "unspecified"))
    )
    (net (code "112") (name "unconnected-(U1B-PD4-Pad72)") (class "Default")
      (node (ref "U1") (pin "72") (pinfunction "PD4_72") (pintype "unspecified"))
    )
    (net (code "113") (name "unconnected-(U1B-PD5-Pad73)") (class "Default")
      (node (ref "U1") (pin "73") (pinfunction "PD5_73") (pintype "unspecified"))
    )
    (net (code "114") (name "unconnected-(U1B-PD6-Pad74)") (class "Default")
      (node (ref "U1") (pin "74") (pinfunction "PD6_74") (pintype "unspecified"))
    )
    (net (code "115") (name "unconnected-(U1B-PD7-Pad75)") (class "Default")
      (node (ref "U1") (pin "75") (pinfunction "PD7_75") (pintype "unspecified"))
    )
    (net (code "116") (name "unconnected-(U1B-PD14-Pad49)") (class "Default")
      (node (ref "U1") (pin "49") (pinfunction "PD14_49") (pintype "unspecified"))
    )
    (net (code "117") (name "unconnected-(U1B-PD15-Pad50)") (class "Default")
      (node (ref "U1") (pin "50") (pinfunction "PD15_50") (pintype "unspecified"))
    )
    (net (code "118") (name "unconnected-(U1B-PE0-Pad83)") (class "Default")
      (node (ref "U1") (pin "83") (pinfunction "PE0_83") (pintype "unspecified"))
    )
    (net (code "119") (name "unconnected-(U1B-PE1-Pad84)") (class "Default")
      (node (ref "U1") (pin "84") (pinfunction "PE1_84") (pintype "unspecified"))
    )
    (net (code "120") (name "unconnected-(U1B-PE2-Pad87)") (class "Default")
      (node (ref "U1") (pin "87") (pinfunction "PE2_87") (pintype "unspecified+no_connect"))
    )
    (net (code "121") (name "unconnected-(U1B-PE3-Pad88)") (class "Default")
      (node (ref "U1") (pin "88") (pinfunction "PE3_88") (pintype "unspecified"))
    )
    (net (code "122") (name "unconnected-(U1B-PE5-Pad90)") (class "Default")
      (node (ref "U1") (pin "90") (pinfunction "PE5_90") (pintype "unspecified"))
    )
    (net (code "123") (name "unconnected-(U2-Pad11)") (class "Default")
      (node (ref "U2") (pin "11") (pinfunction "11_11") (pintype "unspecified"))
    )
    (net (code "124") (name "unconnected-(U2-Pad14)") (class "Default")
      (node (ref "U2") (pin "14") (pinfunction "14_14") (pintype "unspecified"))
    )
    (net (code "125") (name "unconnected-(U2-Pad16)") (class "Default")
      (node (ref "U2") (pin "16") (pinfunction "16_16") (pintype "unspecified"))
    )
    (net (code "126") (name "unconnected-(U2-Pad17)") (class "Default")
      (node (ref "U2") (pin "17") (pinfunction "17_17") (pintype "unspecified"))
    )
    (net (code "127") (name "unconnected-(U3-INTN-Pad4)") (class "Default")
      (node (ref "U3") (pin "4") (pinfunction "INTN_4") (pintype "unspecified"))
    )
    (net (code "128") (name "unconnected-(U3-NC-Pad6)") (class "Default")
      (node (ref "U3") (pin "6") (pinfunction "NC_6") (pintype "unspecified"))
    )
    (net (code "129") (name "unconnected-(U3-NC-Pad7)") (class "Default")
      (node (ref "U3") (pin "7") (pinfunction "NC_7") (pintype "unspecified"))
    )
    (net (code "130") (name "unconnected-(U3-NC-Pad8)") (class "Default")
      (node (ref "U3") (pin "8") (pinfunction "NC_8") (pintype "unspecified"))
    )
    (net (code "131") (name "unconnected-(U14-Q7S-Pad9)") (class "Default")
      (node (ref "U14") (pin "9") (pinfunction "Q7S_9") (pintype "unspecified"))
    )
    (net (code "132") (name "unconnected-(U15-DOUT-Pad2)") (class "Default")
      (node (ref "U15") (pin "2") (pinfunction "DOUT_2") (pintype "unspecified"))
    )
  )
)
